# interface_pt1000.net
KiCad netlist of a schematic drawn in Altium Designer
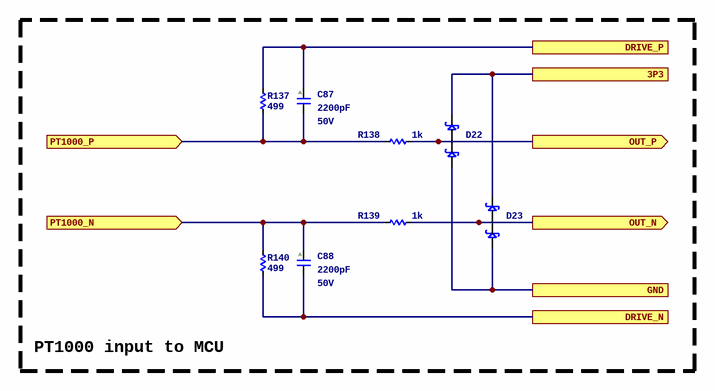
[diagram p0: interface_pt1000.SchDoc]

(export (version "E")
  (design (tool "Eeschema 10.0.6"))
  (components
    (comp (ref "C87")
      (value "CGA2B2X7R1H222M050BA")
      (footprint "C0402_0.55MM")
      (description "CAP CER 2200PF 50V X7R 0402")
      (fields
        (field (name "CAPACITANCE") "2200pF")
        (field (name "VOLTAGE - RATED") "50V")
        (field (name "TOLERANCE") "±20%")
        (field (name "MANUFACTURER") "TDK Corporation")
      )
      (libsource (lib "sscp") (part "__template_cap_auto"))
    )
    (comp (ref "C88")
      (value "CGA2B2X7R1H222M050BA")
      (footprint "C0402_0.55MM")
      (description "CAP CER 2200PF 50V X7R 0402")
      (fields
        (field (name "CAPACITANCE") "2200pF")
        (field (name "VOLTAGE - RATED") "50V")
        (field (name "TOLERANCE") "±20%")
        (field (name "MANUFACTURER") "TDK Corporation")
      )
      (libsource (lib "sscp") (part "__template_cap_auto"))
    )
    (comp (ref "D22")
      (value "BAT54SLT1G")
      (footprint "3SOT23")
      (description "DIODE SCHOTTKY DUAL 30V SOT23")
      (fields (field (name "MANUFACTURER") "ON Semiconductor"))
      (libsource (lib "SSCP") (part "SCHOTTKY_30V_DUAL_BAT54SLT1G"))
    )
    (comp (ref "D23")
      (value "BAT54SLT1G")
      (footprint "3SOT23")
      (description "DIODE SCHOTTKY DUAL 30V SOT23")
      (fields (field (name "MANUFACTURER") "ON Semiconductor"))
      (libsource (lib "SSCP") (part "SCHOTTKY_30V_DUAL_BAT54SLT1G"))
    )
    (comp (ref "R137")
      (value "ERJ-2RKF4990X")
      (footprint "R0402_0.40MM")
      (description "RES SMD 499 OHM 1% 1/10W 0402")
      (fields
        (field (name "RESISTANCE") "499")
        (field (name "TOLERANCE") "±1%")
        (field (name "MANUFACTURER") "Panasonic Electronic Components")
      )
      (libsource (lib "sscp") (part "__template_resistor"))
    )
    (comp (ref "R138")
      (value "~")
      (footprint "R0402_0.40MM")
      (description "RES SMD 1K OHM 1% 1/10W 0402")
      (fields (field (name "RESISTANCE") "1k") (field (name "TOLERANCE") "±1%"))
      (libsource (lib "sscp") (part "__template_resistor"))
    )
    (comp (ref "R139")
      (value "~")
      (footprint "R0402_0.40MM")
      (description "RES SMD 1K OHM 1% 1/10W 0402")
      (fields (field (name "RESISTANCE") "1k") (field (name "TOLERANCE") "±1%"))
      (libsource (lib "sscp") (part "__template_resistor"))
    )
    (comp (ref "R140")
      (value "ERJ-2RKF4990X")
      (footprint "R0402_0.40MM")
      (description "RES SMD 499 OHM 1% 1/10W 0402")
      (fields
        (field (name "RESISTANCE") "499")
        (field (name "TOLERANCE") "±1%")
        (field (name "MANUFACTURER") "Panasonic Electronic Components")
      )
      (libsource (lib "sscp") (part "__template_resistor"))
    )
  )
  (nets
    (net (code "1") (name "/3P3") (class "Default")
      (node (ref "D22") (pin "2") (pintype "passive"))
      (node (ref "D23") (pin "2") (pintype "passive"))
    )
    (net (code "2") (name "/DRIVE_N") (class "Default")
      (node (ref "C88") (pin "2") (pintype "passive"))
      (node (ref "R140") (pin "2") (pintype "passive"))
    )
    (net (code "3") (name "/DRIVE_P") (class "Default")
      (node (ref "C87") (pin "1") (pintype "passive"))
      (node (ref "R137") (pin "1") (pintype "passive"))
    )
    (net (code "4") (name "/GND") (class "Default")
      (node (ref "D22") (pin "1") (pintype "passive"))
      (node (ref "D23") (pin "1") (pintype "passive"))
    )
    (net (code "5") (name "/OUT_N") (class "Default")
      (node (ref "D23") (pin "3") (pintype "passive"))
      (node (ref "R139") (pin "2") (pintype "passive"))
    )
    (net (code "6") (name "/OUT_P") (class "Default")
      (node (ref "D22") (pin "3") (pintype "passive"))
      (node (ref "R138") (pin "2") (pintype "passive"))
    )
    (net (code "7") (name "/PT1000_N") (class "Default")
      (node (ref "C88") (pin "1") (pintype "passive"))
      (node (ref "R139") (pin "1") (pintype "passive"))
      (node (ref "R140") (pin "1") (pintype "passive"))
    )
    (net (code "8") (name "/PT1000_P") (class "Default")
      (node (ref "C87") (pin "2") (pintype "passive"))
      (node (ref "R137") (pin "2") (pintype "passive"))
      (node (ref "R138") (pin "1") (pintype "passive"))
    )
  )
)
